# ProProject_MinSyBo_Star_2024-06-01.net
KiCad netlist of a schematic drawn in EasyEDA Pro
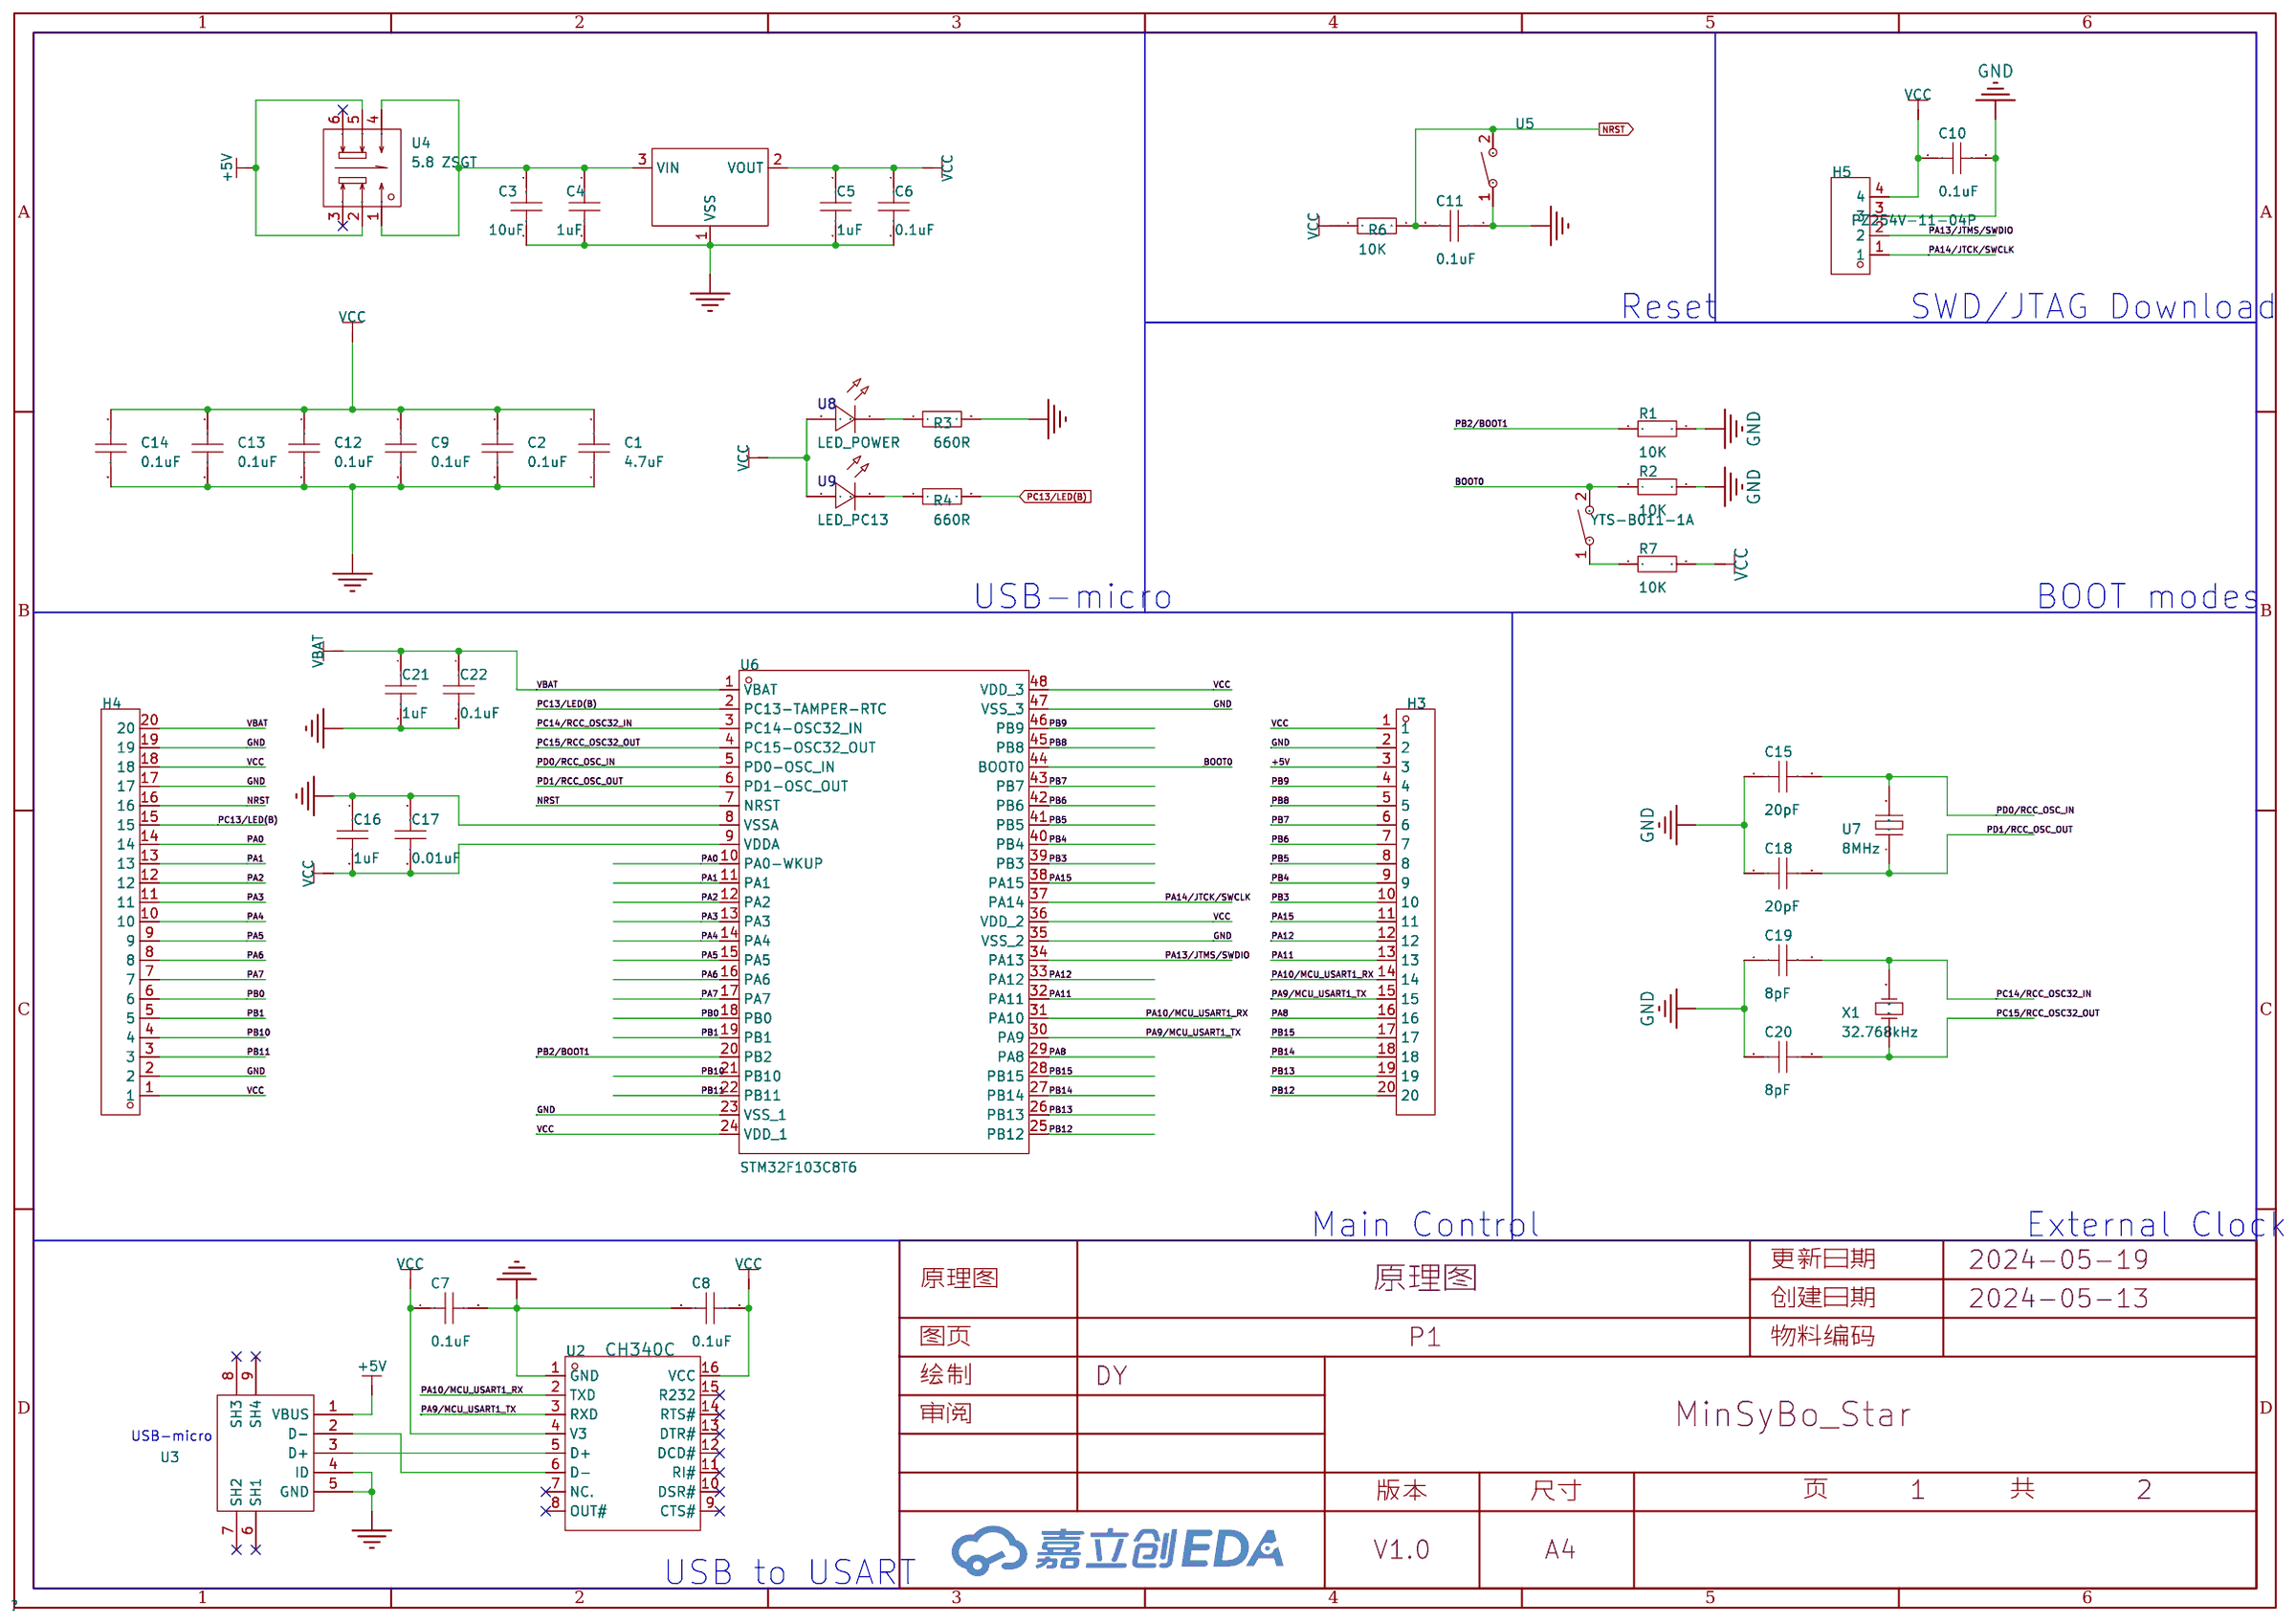
[diagram p0: P1]
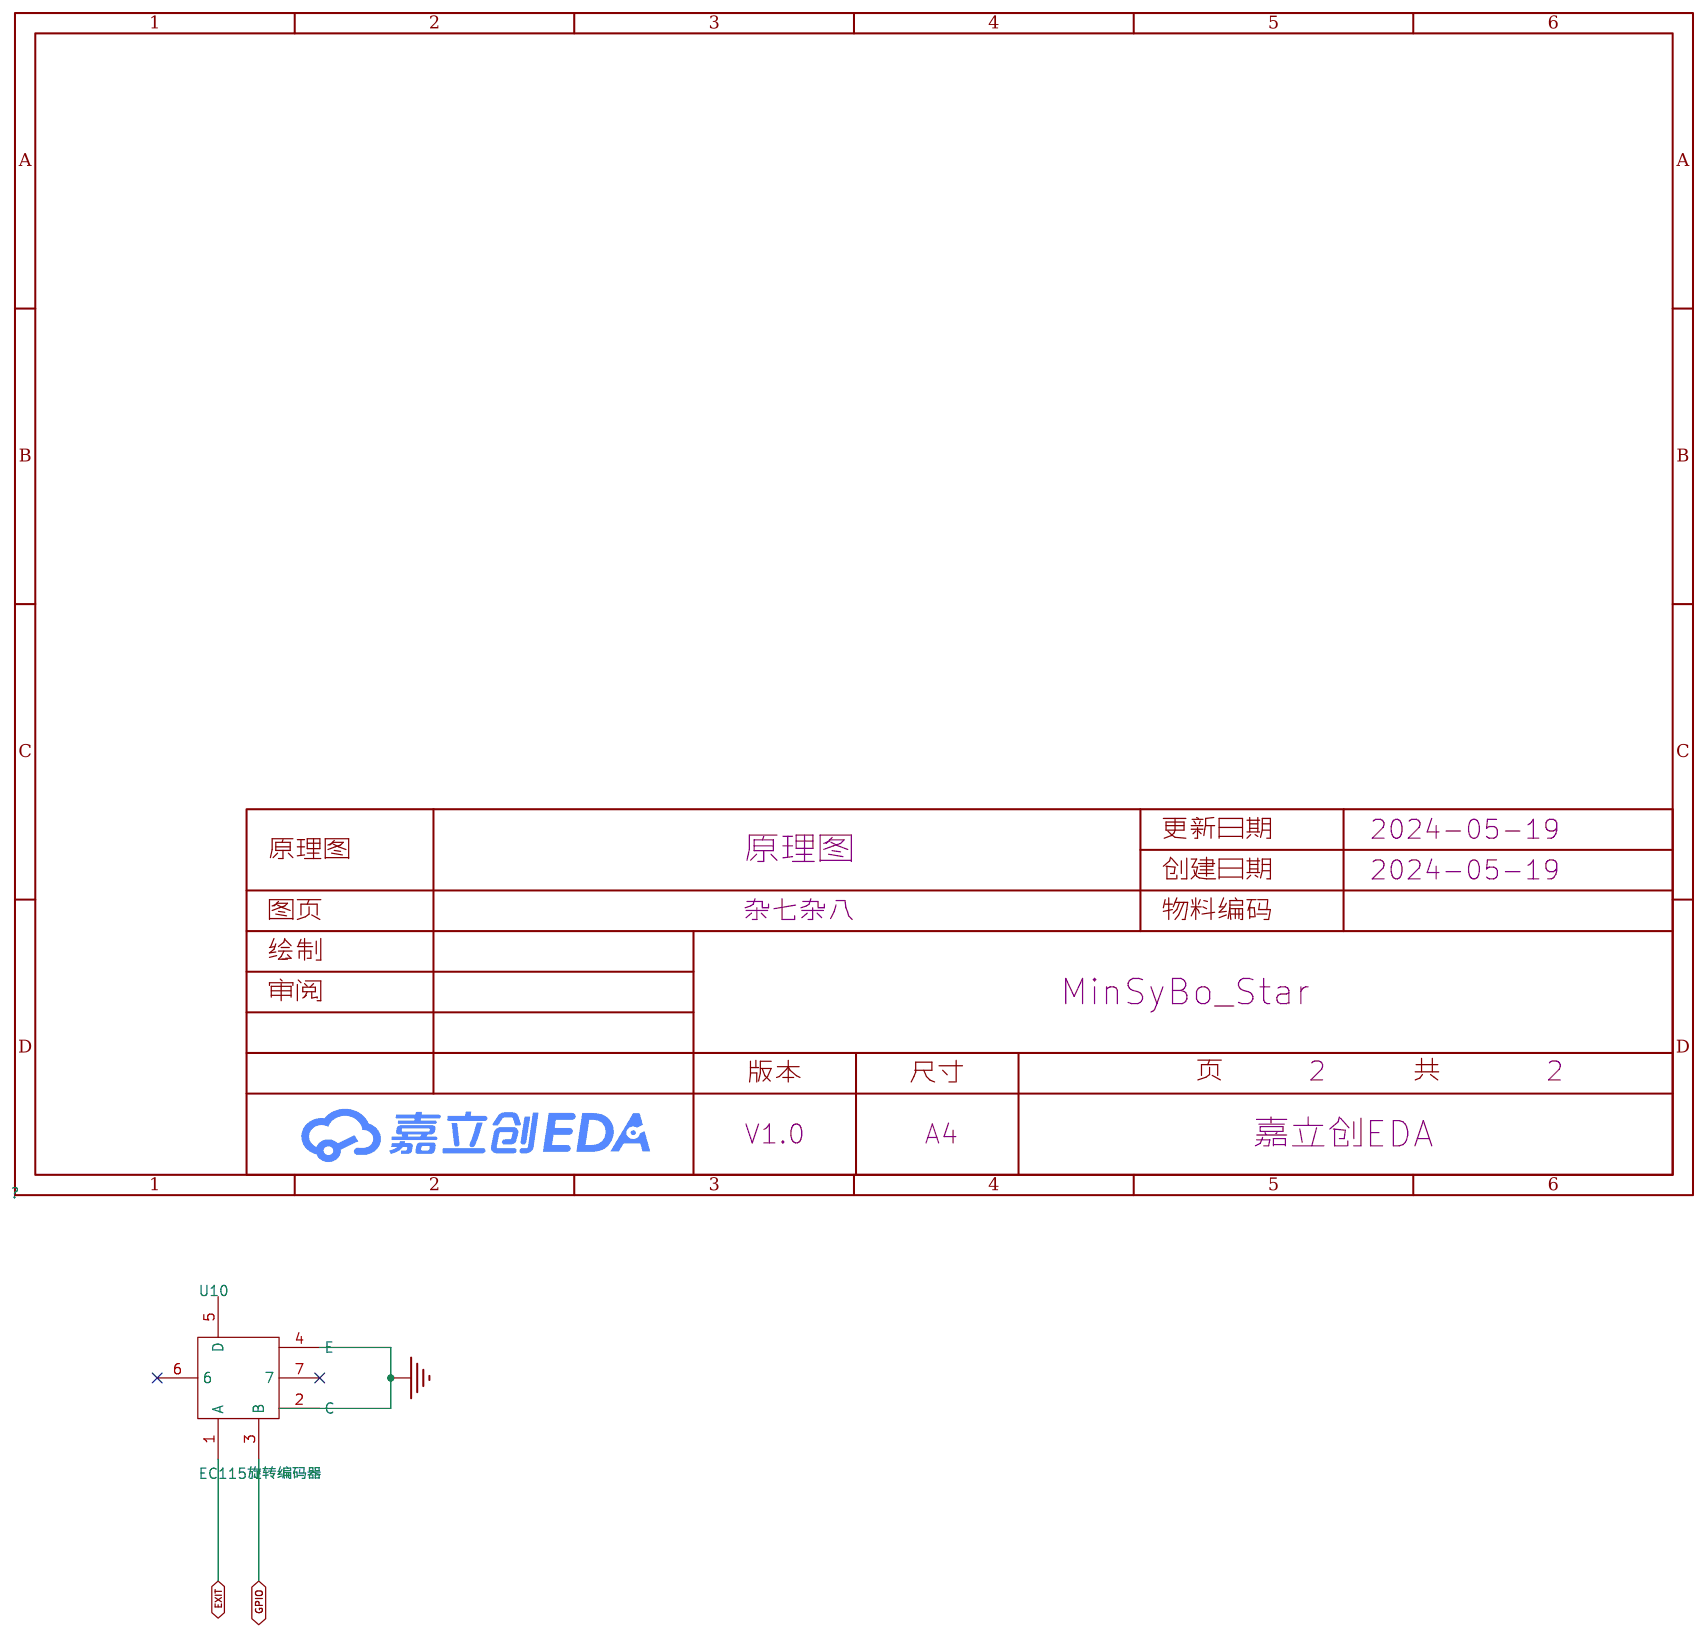
[diagram p1: 杂七杂八]

(export (version "E")
  (design (tool "Eeschema 10.0.6"))
  (components
    (comp (ref "BOOT0")
      (value "YTS-B011-1A")
      (footprint "easyedapro:SW-TH_L6.1-W3.5-P6.60-LS8.0")
      (fields (field (name "Manufacturer") "YIYUAN(怡远)"))
      (libsource (lib "easyedapro") (part "YTS-B011-1A"))
    )
    (comp (ref "C1")
      (value "4.7uF")
      (footprint "easyedapro:C0603")
      (libsource (lib "easyedapro") (part "CapAcitance"))
    )
    (comp (ref "C2")
      (value "100nF")
      (footprint "easyedapro:C0603")
      (libsource (lib "easyedapro") (part "CapAcitance"))
    )
    (comp (ref "C3")
      (value "10uF")
      (footprint "easyedapro:C0603")
      (fields
        (field (name "Manufacturer Part") "CL10A106KP8NNNC")
        (field (name "Manufacturer") "SAMSUNG(三星)")
        (field (name "Tolerance") "±10%")
      )
      (libsource (lib "easyedapro") (part "CapAcitance"))
    )
    (comp (ref "C4")
      (value "1uF")
      (footprint "easyedapro:C0603")
      (libsource (lib "easyedapro") (part "CapAcitance"))
    )
    (comp (ref "C5")
      (value "1uF")
      (footprint "easyedapro:C0603")
      (libsource (lib "easyedapro") (part "CapAcitance"))
    )
    (comp (ref "C6")
      (value "0.1uF")
      (footprint "easyedapro:C0603")
      (libsource (lib "easyedapro") (part "CapAcitance"))
    )
    (comp (ref "C7")
      (value "0.1uF")
      (footprint "easyedapro:C0603")
      (libsource (lib "easyedapro") (part "CapAcitance"))
    )
    (comp (ref "C8")
      (value "0.1uF")
      (footprint "easyedapro:C0603")
      (libsource (lib "easyedapro") (part "CapAcitance"))
    )
    (comp (ref "C9")
      (value "100nF")
      (footprint "easyedapro:C0603")
      (libsource (lib "easyedapro") (part "CapAcitance"))
    )
    (comp (ref "C10")
      (value "0.1uF")
      (footprint "easyedapro:C0603")
      (libsource (lib "easyedapro") (part "CapAcitance"))
    )
    (comp (ref "C11")
      (value "0.1uF")
      (footprint "easyedapro:C0603")
      (libsource (lib "easyedapro") (part "CapAcitance"))
    )
    (comp (ref "C12")
      (value "100nF")
      (footprint "easyedapro:C0603")
      (libsource (lib "easyedapro") (part "CapAcitance"))
    )
    (comp (ref "C13")
      (value "100nF")
      (footprint "easyedapro:C0603")
      (libsource (lib "easyedapro") (part "CapAcitance"))
    )
    (comp (ref "C14")
      (value "100nF")
      (footprint "easyedapro:C0603")
      (libsource (lib "easyedapro") (part "CapAcitance"))
    )
    (comp (ref "C15")
      (value "20pF")
      (footprint "easyedapro:C0603")
      (libsource (lib "easyedapro") (part "CapAcitance"))
    )
    (comp (ref "C16")
      (value "1uF")
      (footprint "easyedapro:C0603")
      (libsource (lib "easyedapro") (part "CapAcitance"))
    )
    (comp (ref "C17")
      (value "0.01uF")
      (footprint "easyedapro:C0603")
      (libsource (lib "easyedapro") (part "CapAcitance"))
    )
    (comp (ref "C18")
      (value "20pF")
      (footprint "easyedapro:C0603")
      (libsource (lib "easyedapro") (part "CapAcitance"))
    )
    (comp (ref "C19")
      (value "8pF")
      (footprint "easyedapro:C0603")
      (libsource (lib "easyedapro") (part "CapAcitance"))
    )
    (comp (ref "C20")
      (value "8pF")
      (footprint "easyedapro:C0603")
      (libsource (lib "easyedapro") (part "CapAcitance"))
    )
    (comp (ref "C21")
      (value "1uF")
      (footprint "easyedapro:C0603")
      (libsource (lib "easyedapro") (part "CapAcitance"))
    )
    (comp (ref "C22")
      (value "0.1uF")
      (footprint "easyedapro:C0603")
      (libsource (lib "easyedapro") (part "CapAcitance"))
    )
    (comp (ref "H3")
      (value "2.54-1*20P直针")
      (footprint "easyedapro:HDR-TH_20P-P2.54-V-M-1")
      (fields (field (name "Manufacturer") "BOOMELE(博穆精密)"))
      (libsource (lib "easyedapro") (part "HDR_2.54-1x20P"))
    )
    (comp (ref "H4")
      (value "2.54-1*20P直针")
      (footprint "easyedapro:HDR-TH_20P-P2.54-V-M-1")
      (fields (field (name "Manufacturer") "BOOMELE(博穆精密)"))
      (libsource (lib "easyedapro") (part "HDR_2.54-1x20P"))
    )
    (comp (ref "H5")
      (value "PZ254V-11-04P")
      (footprint "easyedapro:HDR-TH_4P-P2.54-V-M")
      (fields (field (name "Manufacturer") "XFCN(兴飞)"))
      (libsource (lib "easyedapro") (part "PZ254V-11-04P"))
    )
    (comp (ref "R1") (value "10K") (footprint "easyedapro:R0603") (libsource (lib "easyedapro") (part "电阻")))
    (comp (ref "R2") (value "10K") (footprint "easyedapro:R0603") (libsource (lib "easyedapro") (part "电阻")))
    (comp (ref "R3") (value "660R") (footprint "easyedapro:R0603") (libsource (lib "easyedapro") (part "电阻")))
    (comp (ref "R4") (value "660R") (footprint "easyedapro:R0603") (libsource (lib "easyedapro") (part "电阻")))
    (comp (ref "R6") (value "10K") (footprint "easyedapro:R0603") (libsource (lib "easyedapro") (part "电阻")))
    (comp (ref "R7") (value "10K") (footprint "easyedapro:R0603") (libsource (lib "easyedapro") (part "电阻")))
    (comp (ref "U1")
      (value "XC6206P332MR")
      (footprint "easyedapro:SOT-23-3_L2.9-W1.3-P1.90-LS2.4-BR")
      (description "输出类型:固定;最大输入电压:8V;输出电压:3.3V;最大输出电流:300mA;输出极性:正极;")
      (fields (field (name "Manufacturer") "HXY MOSFET(华轩阳电子)"))
      (libsource (lib "easyedapro") (part "XC6206P332MR_C5148692"))
    )
    (comp (ref "U2")
      (value "CH340C")
      (footprint "easyedapro:SOP-16_L10.0-W3.9-P1.27-LS6.0-BL")
      (description "应用功能:收发器;接口协议:USB 2.0;数据速率:2Mbps;")
      (fields (field (name "Manufacturer") "WCH(南京沁恒)"))
      (libsource (lib "easyedapro") (part "CH340C"))
    )
    (comp (ref "U3")
      (value "MicroXNJ")
      (footprint "easyedapro:MICRO-USB-SMD_MICROXNJ")
      (description "连接器类型:Micro-B;标准:USB 2.0;公母:母;端口数量:1;触点数量:5P;安装方式:卧贴;额定电流 - 电源:1A;工作温度范围:-20°C~+85°C;")
      (fields (field (name "Manufacturer") "SHOU HAN(首韩)"))
      (libsource (lib "easyedapro") (part "MICROXNJ"))
    )
    (comp (ref "U4")
      (value "5.8 ZSGT")
      (footprint "easyedapro:SW-TH_5.8ZSGT")
      (description "电路结构:双刀双掷;自锁/无锁:自锁;安装方式:直插;触点电流:110mA;额定电压 (DC):30V;带灯:不带;作用力:150gf;机械寿命:10万次;")
      (fields (field (name "Manufacturer") "SHOU HAN(首韩)"))
      (libsource (lib "easyedapro") (part "5.8 ZSGT"))
    )
    (comp (ref "U5")
      (value "YTS-B011-1A")
      (footprint "easyedapro:SW-TH_L6.1-W3.5-P6.60-LS8.0")
      (fields (field (name "Manufacturer") "YIYUAN(怡远)"))
      (libsource (lib "easyedapro") (part "YTS-B011-1A"))
    )
    (comp (ref "U6")
      (value "STM32F103C8T6")
      (footprint "easyedapro:LQFP-48_L7.0-W7.0-P0.50-LS9.0-BL")
      (description "CPU内核:ARM-M3;程序存储容量:64KB;RAM总容量:20KB;GPIO端口数量:37;工作电压范围:2V~3.6V;CPU最大主频:72MHz;程序存储器类型:FLASH;")
      (fields (field (name "Manufacturer") "ST(意法半导体)"))
      (libsource (lib "easyedapro") (part "STM32F103C8T6"))
    )
    (comp (ref "U7")
      (value "8MHz")
      (footprint "easyedapro:HC-49SMD_L11.1-W4.8")
      (description "晶振类型:贴片晶振;频率:8MHz;常温频差:±10ppm;外接负载电容:20pF;频率稳定度(全温):±30ppm;")
      (fields (field (name "Manufacturer Part") "RC08000619") (field (name "Manufacturer") "TROQ(创捷)"))
      (libsource (lib "easyedapro") (part "RC08000619"))
    )
    (comp (ref "U8")
      (value "LED_POWER")
      (footprint "easyedapro:LED_0603")
      (libsource (lib "easyedapro") (part "LED_G"))
    )
    (comp (ref "U9")
      (value "LED_PC13")
      (footprint "easyedapro:LED_0603")
      (libsource (lib "easyedapro") (part "LED_B"))
    )
    (comp (ref "X1")
      (value "32.768kHz")
      (footprint "easyedapro:OSC-TH_BD3.8-P0.50")
      (description "晶振类型:直插晶振;频率:32.768kHz;常温频差:±20ppm;外接负载电容:12.5pF;频率稳定度(全温):±20ppm;")
      (fields (field (name "Manufacturer Part") "K383276812520") (field (name "Manufacturer") "KYX(凯越翔)"))
      (libsource (lib "easyedapro") (part "K383276812520"))
    )
    (comp (ref "U10")
      (value "EC115旋转编码器")
      (footprint "easyedapro:SW-SMD_EC115_C9900036245")
      (libsource (lib "easyedapro") (part "EC115旋转编码器"))
    )
  )
  (nets
    (net (code "1") (name "+5V") (class "Default")
      (node (ref "H3") (pin "3") (pinfunction "3_3") (pintype "input"))
      (node (ref "U3") (pin "1") (pinfunction "VBUS_1") (pintype "unspecified"))
      (node (ref "U4") (pin "2") (pinfunction "2_2") (pintype "unspecified"))
      (node (ref "U4") (pin "5") (pinfunction "5_5") (pintype "unspecified"))
    )
    (net (code "2") (name "BOOT0") (class "Default")
      (node (ref "BOOT0") (pin "2") (pinfunction "2_2") (pintype "unspecified"))
      (node (ref "R2") (pin "1") (pinfunction "1_1") (pintype "input"))
      (node (ref "U6") (pin "44") (pinfunction "BOOT0_44") (pintype "unspecified"))
    )
    (net (code "3") (name "EXIT") (class "Default")
      (node (ref "U10") (pin "1") (pinfunction "A_1") (pintype "unspecified"))
    )
    (net (code "4") (name "GND") (class "Default")
      (node (ref "C1") (pin "1") (pinfunction "1_1") (pintype "input"))
      (node (ref "C10") (pin "2") (pinfunction "2_2") (pintype "input"))
      (node (ref "C11") (pin "1") (pinfunction "1_1") (pintype "input"))
      (node (ref "C12") (pin "2") (pinfunction "2_2") (pintype "input"))
      (node (ref "C13") (pin "2") (pinfunction "2_2") (pintype "input"))
      (node (ref "C14") (pin "2") (pinfunction "2_2") (pintype "input"))
      (node (ref "C15") (pin "1") (pinfunction "1_1") (pintype "input"))
      (node (ref "C16") (pin "1") (pinfunction "1_1") (pintype "input"))
      (node (ref "C17") (pin "1") (pinfunction "1_1") (pintype "input"))
      (node (ref "C18") (pin "1") (pinfunction "1_1") (pintype "input"))
      (node (ref "C19") (pin "1") (pinfunction "1_1") (pintype "input"))
      (node (ref "C2") (pin "2") (pinfunction "2_2") (pintype "input"))
      (node (ref "C20") (pin "1") (pinfunction "1_1") (pintype "input"))
      (node (ref "C21") (pin "2") (pinfunction "2_2") (pintype "input"))
      (node (ref "C22") (pin "2") (pinfunction "2_2") (pintype "input"))
      (node (ref "C3") (pin "2") (pinfunction "2_2") (pintype "input"))
      (node (ref "C4") (pin "2") (pinfunction "2_2") (pintype "input"))
      (node (ref "C5") (pin "2") (pinfunction "2_2") (pintype "input"))
      (node (ref "C6") (pin "2") (pinfunction "2_2") (pintype "input"))
      (node (ref "C7") (pin "2") (pinfunction "2_2") (pintype "input"))
      (node (ref "C8") (pin "1") (pinfunction "1_1") (pintype "input"))
      (node (ref "C9") (pin "2") (pinfunction "2_2") (pintype "input"))
      (node (ref "H3") (pin "2") (pinfunction "2_2") (pintype "input"))
      (node (ref "H4") (pin "17") (pinfunction "17_17") (pintype "input"))
      (node (ref "H4") (pin "19") (pinfunction "19_19") (pintype "input"))
      (node (ref "H4") (pin "2") (pinfunction "2_2") (pintype "input"))
      (node (ref "H5") (pin "3") (pinfunction "3_3") (pintype "unspecified"))
      (node (ref "R1") (pin "1") (pinfunction "1_1") (pintype "input"))
      (node (ref "R2") (pin "2") (pinfunction "2_2") (pintype "input"))
      (node (ref "R3") (pin "2") (pinfunction "2_2") (pintype "input"))
      (node (ref "U1") (pin "1") (pinfunction "VSS_1") (pintype "unspecified"))
      (node (ref "U10") (pin "2") (pinfunction "C_2") (pintype "unspecified"))
      (node (ref "U2") (pin "1") (pinfunction "GND_1") (pintype "unspecified"))
      (node (ref "U3") (pin "4") (pinfunction "ID_4") (pintype "unspecified"))
      (node (ref "U3") (pin "5") (pinfunction "GND_5") (pintype "unspecified"))
      (node (ref "U5") (pin "1") (pinfunction "1_1") (pintype "unspecified"))
      (node (ref "U6") (pin "23") (pinfunction "VSS_1_23") (pintype "unspecified"))
      (node (ref "U6") (pin "35") (pinfunction "VSS_2_35") (pintype "unspecified"))
      (node (ref "U6") (pin "47") (pinfunction "VSS_3_47") (pintype "unspecified"))
      (node (ref "U6") (pin "8") (pinfunction "VSSA_8") (pintype "unspecified"))
    )
    (net (code "5") (name "GPIO") (class "Default")
      (node (ref "U10") (pin "3") (pinfunction "B_3") (pintype "unspecified"))
    )
    (net (code "6") (name "NRST") (class "Default")
      (node (ref "C11") (pin "2") (pinfunction "2_2") (pintype "input"))
      (node (ref "H4") (pin "16") (pinfunction "16_16") (pintype "input"))
      (node (ref "R6") (pin "2") (pinfunction "2_2") (pintype "input"))
      (node (ref "U5") (pin "2") (pinfunction "2_2") (pintype "unspecified"))
      (node (ref "U6") (pin "7") (pinfunction "NRST_7") (pintype "unspecified"))
    )
    (net (code "7") (name "Net-(BOOT0-Pad1)") (class "Default")
      (node (ref "BOOT0") (pin "1") (pinfunction "1_1") (pintype "unspecified"))
      (node (ref "R7") (pin "1") (pinfunction "1_1") (pintype "input"))
    )
    (net (code "8") (name "Net-(U1-VIN)") (class "Default")
      (node (ref "C3") (pin "1") (pinfunction "1_1") (pintype "input"))
      (node (ref "C4") (pin "1") (pinfunction "1_1") (pintype "input"))
      (node (ref "U1") (pin "3") (pinfunction "VIN_3") (pintype "unspecified"))
      (node (ref "U4") (pin "1") (pinfunction "1_1") (pintype "unspecified"))
      (node (ref "U4") (pin "4") (pinfunction "4_4") (pintype "unspecified"))
    )
    (net (code "9") (name "Net-(U2-D+)") (class "Default")
      (node (ref "U2") (pin "5") (pinfunction "D+_5") (pintype "unspecified"))
      (node (ref "U3") (pin "3") (pinfunction "D+_3") (pintype "unspecified"))
    )
    (net (code "10") (name "Net-(U2-D-)") (class "Default")
      (node (ref "U2") (pin "6") (pinfunction "D-_6") (pintype "unspecified"))
      (node (ref "U3") (pin "2") (pinfunction "D-_2") (pintype "unspecified"))
    )
    (net (code "11") (name "Net-(U8-C)") (class "Default")
      (node (ref "R3") (pin "1") (pinfunction "1_1") (pintype "input"))
      (node (ref "U8") (pin "1") (pinfunction "C_1") (pintype "input"))
    )
    (net (code "12") (name "Net-(U9-C)") (class "Default")
      (node (ref "R4") (pin "1") (pinfunction "1_1") (pintype "input"))
      (node (ref "U9") (pin "1") (pinfunction "C_1") (pintype "input"))
    )
    (net (code "13") (name "PA0") (class "Default")
      (node (ref "H4") (pin "14") (pinfunction "14_14") (pintype "input"))
      (node (ref "U6") (pin "10") (pinfunction "PA0-WKUP_10") (pintype "unspecified"))
    )
    (net (code "14") (name "PA1") (class "Default")
      (node (ref "H4") (pin "13") (pinfunction "13_13") (pintype "input"))
      (node (ref "U6") (pin "11") (pinfunction "PA1_11") (pintype "unspecified"))
    )
    (net (code "15") (name "PA2") (class "Default")
      (node (ref "H4") (pin "12") (pinfunction "12_12") (pintype "input"))
      (node (ref "U6") (pin "12") (pinfunction "PA2_12") (pintype "unspecified"))
    )
    (net (code "16") (name "PA3") (class "Default")
      (node (ref "H4") (pin "11") (pinfunction "11_11") (pintype "input"))
      (node (ref "U6") (pin "13") (pinfunction "PA3_13") (pintype "unspecified"))
    )
    (net (code "17") (name "PA4") (class "Default")
      (node (ref "H4") (pin "10") (pinfunction "10_10") (pintype "input"))
      (node (ref "U6") (pin "14") (pinfunction "PA4_14") (pintype "unspecified"))
    )
    (net (code "18") (name "PA5") (class "Default")
      (node (ref "H4") (pin "9") (pinfunction "9_9") (pintype "input"))
      (node (ref "U6") (pin "15") (pinfunction "PA5_15") (pintype "unspecified"))
    )
    (net (code "19") (name "PA6") (class "Default")
      (node (ref "H4") (pin "8") (pinfunction "8_8") (pintype "input"))
      (node (ref "U6") (pin "16") (pinfunction "PA6_16") (pintype "unspecified"))
    )
    (net (code "20") (name "PA7") (class "Default")
      (node (ref "H4") (pin "7") (pinfunction "7_7") (pintype "input"))
      (node (ref "U6") (pin "17") (pinfunction "PA7_17") (pintype "unspecified"))
    )
    (net (code "21") (name "PA8") (class "Default")
      (node (ref "H3") (pin "16") (pinfunction "16_16") (pintype "input"))
      (node (ref "U6") (pin "29") (pinfunction "PA8_29") (pintype "unspecified"))
    )
    (net (code "22") (name "PA9{slash}MCU_USART1_TX") (class "Default")
      (node (ref "H3") (pin "15") (pinfunction "15_15") (pintype "input"))
      (node (ref "U2") (pin "3") (pinfunction "RXD_3") (pintype "unspecified"))
      (node (ref "U6") (pin "30") (pinfunction "PA9_30") (pintype "unspecified"))
    )
    (net (code "23") (name "PA10{slash}MCU_USART1_RX") (class "Default")
      (node (ref "H3") (pin "14") (pinfunction "14_14") (pintype "input"))
      (node (ref "U2") (pin "2") (pinfunction "TXD_2") (pintype "unspecified"))
      (node (ref "U6") (pin "31") (pinfunction "PA10_31") (pintype "unspecified"))
    )
    (net (code "24") (name "PA11") (class "Default")
      (node (ref "H3") (pin "13") (pinfunction "13_13") (pintype "input"))
      (node (ref "U6") (pin "32") (pinfunction "PA11_32") (pintype "unspecified"))
    )
    (net (code "25") (name "PA12") (class "Default")
      (node (ref "H3") (pin "12") (pinfunction "12_12") (pintype "input"))
      (node (ref "U6") (pin "33") (pinfunction "PA12_33") (pintype "unspecified"))
    )
    (net (code "26") (name "PA13{slash}JTMS{slash}SWDIO") (class "Default")
      (node (ref "H5") (pin "2") (pinfunction "2_2") (pintype "unspecified"))
      (node (ref "U6") (pin "34") (pinfunction "PA13_34") (pintype "unspecified"))
    )
    (net (code "27") (name "PA14{slash}JTCK{slash}SWCLK") (class "Default")
      (node (ref "H5") (pin "1") (pinfunction "1_1") (pintype "unspecified"))
      (node (ref "U6") (pin "37") (pinfunction "PA14_37") (pintype "unspecified"))
    )
    (net (code "28") (name "PA15") (class "Default")
      (node (ref "H3") (pin "11") (pinfunction "11_11") (pintype "input"))
      (node (ref "U6") (pin "38") (pinfunction "PA15_38") (pintype "unspecified"))
    )
    (net (code "29") (name "PB0") (class "Default")
      (node (ref "H4") (pin "6") (pinfunction "6_6") (pintype "input"))
      (node (ref "U6") (pin "18") (pinfunction "PB0_18") (pintype "unspecified"))
    )
    (net (code "30") (name "PB1") (class "Default")
      (node (ref "H4") (pin "5") (pinfunction "5_5") (pintype "input"))
      (node (ref "U6") (pin "19") (pinfunction "PB1_19") (pintype "unspecified"))
    )
    (net (code "31") (name "PB2{slash}BOOT1") (class "Default")
      (node (ref "R1") (pin "2") (pinfunction "2_2") (pintype "input"))
      (node (ref "U6") (pin "20") (pinfunction "PB2_20") (pintype "unspecified"))
    )
    (net (code "32") (name "PB3") (class "Default")
      (node (ref "H3") (pin "10") (pinfunction "10_10") (pintype "input"))
      (node (ref "U6") (pin "39") (pinfunction "PB3_39") (pintype "unspecified"))
    )
    (net (code "33") (name "PB4") (class "Default")
      (node (ref "H3") (pin "9") (pinfunction "9_9") (pintype "input"))
      (node (ref "U6") (pin "40") (pinfunction "PB4_40") (pintype "unspecified"))
    )
    (net (code "34") (name "PB5") (class "Default")
      (node (ref "H3") (pin "8") (pinfunction "8_8") (pintype "input"))
      (node (ref "U6") (pin "41") (pinfunction "PB5_41") (pintype "unspecified"))
    )
    (net (code "35") (name "PB6") (class "Default")
      (node (ref "H3") (pin "7") (pinfunction "7_7") (pintype "input"))
      (node (ref "U6") (pin "42") (pinfunction "PB6_42") (pintype "unspecified"))
    )
    (net (code "36") (name "PB7") (class "Default")
      (node (ref "H3") (pin "6") (pinfunction "6_6") (pintype "input"))
      (node (ref "U6") (pin "43") (pinfunction "PB7_43") (pintype "unspecified"))
    )
    (net (code "37") (name "PB8") (class "Default")
      (node (ref "H3") (pin "5") (pinfunction "5_5") (pintype "input"))
      (node (ref "U6") (pin "45") (pinfunction "PB8_45") (pintype "unspecified"))
    )
    (net (code "38") (name "PB9") (class "Default")
      (node (ref "H3") (pin "4") (pinfunction "4_4") (pintype "input"))
      (node (ref "U6") (pin "46") (pinfunction "PB9_46") (pintype "unspecified"))
    )
    (net (code "39") (name "PB10") (class "Default")
      (node (ref "H4") (pin "4") (pinfunction "4_4") (pintype "input"))
      (node (ref "U6") (pin "21") (pinfunction "PB10_21") (pintype "unspecified"))
    )
    (net (code "40") (name "PB11") (class "Default")
      (node (ref "H4") (pin "3") (pinfunction "3_3") (pintype "input"))
      (node (ref "U6") (pin "22") (pinfunction "PB11_22") (pintype "unspecified"))
    )
    (net (code "41") (name "PB12") (class "Default")
      (node (ref "H3") (pin "20") (pinfunction "20_20") (pintype "input"))
      (node (ref "U6") (pin "25") (pinfunction "PB12_25") (pintype "unspecified"))
    )
    (net (code "42") (name "PB13") (class "Default")
      (node (ref "H3") (pin "19") (pinfunction "19_19") (pintype "input"))
      (node (ref "U6") (pin "26") (pinfunction "PB13_26") (pintype "unspecified"))
    )
    (net (code "43") (name "PB14") (class "Default")
      (node (ref "H3") (pin "18") (pinfunction "18_18") (pintype "input"))
      (node (ref "U6") (pin "27") (pinfunction "PB14_27") (pintype "unspecified"))
    )
    (net (code "44") (name "PB15") (class "Default")
      (node (ref "H3") (pin "17") (pinfunction "17_17") (pintype "input"))
      (node (ref "U6") (pin "28") (pinfunction "PB15_28") (pintype "unspecified"))
    )
    (net (code "45") (name "PC13{slash}LED(B)") (class "Default")
      (node (ref "H4") (pin "15") (pinfunction "15_15") (pintype "input"))
      (node (ref "R4") (pin "2") (pinfunction "2_2") (pintype "input"))
      (node (ref "U6") (pin "2") (pinfunction "PC13-TAMPER-RTC_2") (pintype "unspecified"))
    )
    (net (code "46") (name "PC14{slash}RCC_OSC32_IN") (class "Default")
      (node (ref "C19") (pin "2") (pinfunction "2_2") (pintype "input"))
      (node (ref "U6") (pin "3") (pinfunction "PC14-OSC32_IN_3") (pintype "unspecified"))
      (node (ref "X1") (pin "2") (pinfunction "OSC2_2") (pintype "unspecified"))
    )
    (net (code "47") (name "PC15{slash}RCC_OSC32_OUT") (class "Default")
      (node (ref "C20") (pin "2") (pinfunction "2_2") (pintype "input"))
      (node (ref "U6") (pin "4") (pinfunction "PC15-OSC32_OUT_4") (pintype "unspecified"))
      (node (ref "X1") (pin "1") (pinfunction "OSC1_1") (pintype "unspecified"))
    )
    (net (code "48") (name "PD0{slash}RCC_OSC_IN") (class "Default")
      (node (ref "C15") (pin "2") (pinfunction "2_2") (pintype "input"))
      (node (ref "U6") (pin "5") (pinfunction "PD0-OSC_IN_5") (pintype "unspecified"))
      (node (ref "U7") (pin "2") (pinfunction "GND_2") (pintype "input"))
    )
    (net (code "49") (name "PD1{slash}RCC_OSC_OUT") (class "Default")
      (node (ref "C18") (pin "2") (pinfunction "2_2") (pintype "input"))
      (node (ref "U6") (pin "6") (pinfunction "PD1-OSC_OUT_6") (pintype "unspecified"))
      (node (ref "U7") (pin "1") (pinfunction "1_1") (pintype "input"))
    )
    (net (code "50") (name "VBAT") (class "Default")
      (node (ref "C21") (pin "1") (pinfunction "1_1") (pintype "input"))
      (node (ref "C22") (pin "1") (pinfunction "1_1") (pintype "input"))
      (node (ref "H4") (pin "20") (pinfunction "20_20") (pintype "input"))
      (node (ref "U6") (pin "1") (pinfunction "VBAT_1") (pintype "unspecified"))
    )
    (net (code "51") (name "VCC") (class "Default")
      (node (ref "C1") (pin "2") (pinfunction "2_2") (pintype "input"))
      (node (ref "C10") (pin "1") (pinfunction "1_1") (pintype "input"))
      (node (ref "C12") (pin "1") (pinfunction "1_1") (pintype "input"))
      (node (ref "C13") (pin "1") (pinfunction "1_1") (pintype "input"))
      (node (ref "C14") (pin "1") (pinfunction "1_1") (pintype "input"))
      (node (ref "C16") (pin "2") (pinfunction "2_2") (pintype "input"))
      (node (ref "C17") (pin "2") (pinfunction "2_2") (pintype "input"))
      (node (ref "C2") (pin "1") (pinfunction "1_1") (pintype "input"))
      (node (ref "C5") (pin "1") (pinfunction "1_1") (pintype "input"))
      (node (ref "C6") (pin "1") (pinfunction "1_1") (pintype "input"))
      (node (ref "C7") (pin "1") (pinfunction "1_1") (pintype "input"))
      (node (ref "C8") (pin "2") (pinfunction "2_2") (pintype "input"))
      (node (ref "C9") (pin "1") (pinfunction "1_1") (pintype "input"))
      (node (ref "H3") (pin "1") (pinfunction "1_1") (pintype "input"))
      (node (ref "H4") (pin "1") (pinfunction "1_1") (pintype "input"))
      (node (ref "H4") (pin "18") (pinfunction "18_18") (pintype "input"))
      (node (ref "H5") (pin "4") (pinfunction "4_4") (pintype "unspecified"))
      (node (ref "R6") (pin "1") (pinfunction "1_1") (pintype "input"))
      (node (ref "R7") (pin "2") (pinfunction "2_2") (pintype "input"))
      (node (ref "U1") (pin "2") (pinfunction "VOUT_2") (pintype "unspecified"))
      (node (ref "U2") (pin "16") (pinfunction "VCC_16") (pintype "unspecified"))
      (node (ref "U2") (pin "4") (pinfunction "V3_4") (pintype "unspecified"))
      (node (ref "U6") (pin "24") (pinfunction "VDD_1_24") (pintype "unspecified"))
      (node (ref "U6") (pin "36") (pinfunction "VDD_2_36") (pintype "unspecified"))
      (node (ref "U6") (pin "48") (pinfunction "VDD_3_48") (pintype "unspecified"))
      (node (ref "U6") (pin "9") (pinfunction "VDDA_9") (pintype "unspecified"))
      (node (ref "U8") (pin "2") (pinfunction "A_2") (pintype "input"))
      (node (ref "U9") (pin "2") (pinfunction "A_2") (pintype "input"))
    )
    (net (code "52") (name "unconnected-(U2-CTS#-Pad9)") (class "Default")
      (node (ref "U2") (pin "9") (pinfunction "CTS#_9") (pintype "unspecified+no_connect"))
    )
    (net (code "53") (name "unconnected-(U2-DCD#-Pad12)") (class "Default")
      (node (ref "U2") (pin "12") (pinfunction "DCD#_12") (pintype "unspecified+no_connect"))
    )
    (net (code "54") (name "unconnected-(U2-DSR#-Pad10)") (class "Default")
      (node (ref "U2") (pin "10") (pinfunction "DSR#_10") (pintype "unspecified+no_connect"))
    )
    (net (code "55") (name "unconnected-(U2-DTR#-Pad13)") (class "Default")
      (node (ref "U2") (pin "13") (pinfunction "DTR#_13") (pintype "unspecified+no_connect"))
    )
    (net (code "56") (name "unconnected-(U2-NC.-Pad7)") (class "Default")
      (node (ref "U2") (pin "7") (pinfunction "NC._7") (pintype "unspecified+no_connect"))
    )
    (net (code "57") (name "unconnected-(U2-OUT#-Pad8)") (class "Default")
      (node (ref "U2") (pin "8") (pinfunction "OUT#_8") (pintype "unspecified+no_connect"))
    )
    (net (code "58") (name "unconnected-(U2-R232-Pad15)") (class "Default")
      (node (ref "U2") (pin "15") (pinfunction "R232_15") (pintype "unspecified+no_connect"))
    )
    (net (code "59") (name "unconnected-(U2-RI#-Pad11)") (class "Default")
      (node (ref "U2") (pin "11") (pinfunction "RI#_11") (pintype "unspecified+no_connect"))
    )
    (net (code "60") (name "unconnected-(U2-RTS#-Pad14)") (class "Default")
      (node (ref "U2") (pin "14") (pinfunction "RTS#_14") (pintype "unspecified+no_connect"))
    )
    (net (code "61") (name "unconnected-(U3-SH1-Pad6)") (class "Default")
      (node (ref "U3") (pin "6") (pinfunction "SH1_6") (pintype "unspecified+no_connect"))
    )
    (net (code "62") (name "unconnected-(U3-SH2-Pad7)") (class "Default")
      (node (ref "U3") (pin "7") (pinfunction "SH2_7") (pintype "unspecified+no_connect"))
    )
    (net (code "63") (name "unconnected-(U3-SH3-Pad8)") (class "Default")
      (node (ref "U3") (pin "8") (pinfunction "SH3_8") (pintype "unspecified+no_connect"))
    )
    (net (code "64") (name "unconnected-(U3-SH4-Pad9)") (class "Default")
      (node (ref "U3") (pin "9") (pinfunction "SH4_9") (pintype "unspecified+no_connect"))
    )
    (net (code "65") (name "unconnected-(U4-Pad3)") (class "Default")
      (node (ref "U4") (pin "3") (pinfunction "3_3") (pintype "unspecified+no_connect"))
    )
    (net (code "66") (name "unconnected-(U4-Pad6)") (class "Default")
      (node (ref "U4") (pin "6") (pinfunction "6_6") (pintype "unspecified+no_connect"))
    )
    (net (code "67") (name "unconnected-(U10-D-Pad5)") (class "Default")
      (node (ref "U10") (pin "5") (pinfunction "D_5") (pintype "unspecified"))
    )
    (net (code "68") (name "unconnected-(U10-E-Pad4)") (class "Default")
      (node (ref "U10") (pin "4") (pinfunction "E_4") (pintype "unspecified"))
    )
    (net (code "69") (name "unconnected-(U10-Pad6)") (class "Default")
      (node (ref "U10") (pin "6") (pinfunction "6_6") (pintype "unspecified+no_connect"))
    )
    (net (code "70") (name "unconnected-(U10-Pad7)") (class "Default")
      (node (ref "U10") (pin "7") (pinfunction "7_7") (pintype "unspecified+no_connect"))
    )
  )
)
